# doan2.net
KiCad netlist of a schematic drawn in Altium Designer
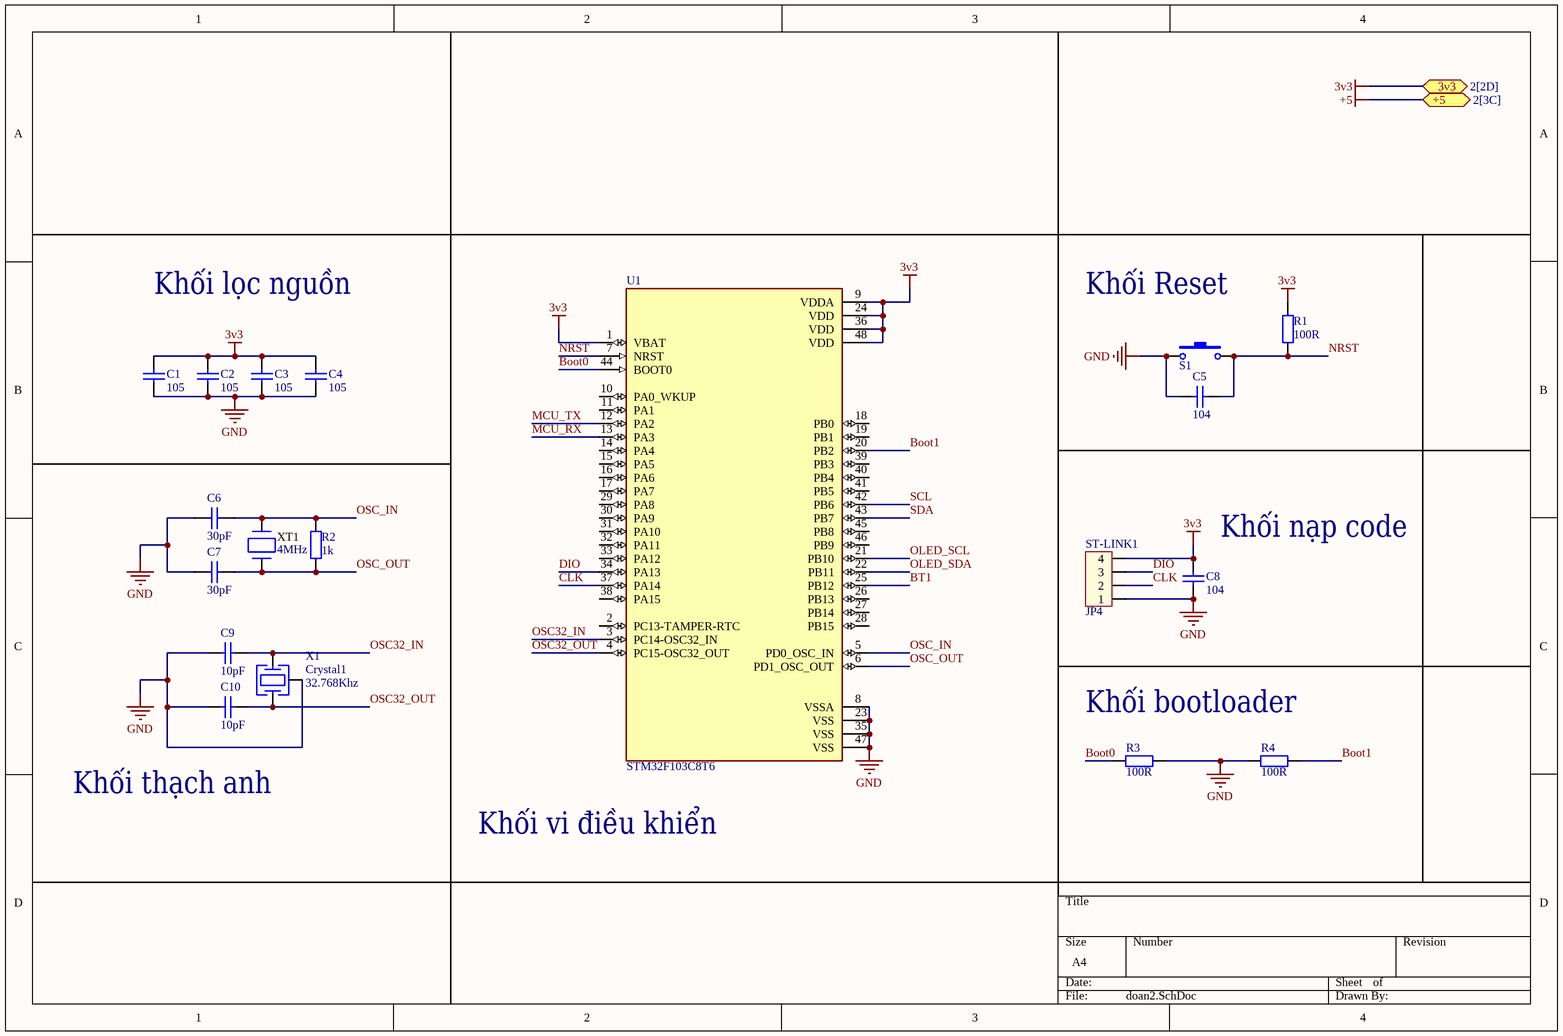
[diagram p0: doan2.SchDoc]

(export (version "E")
  (design (tool "Eeschema 10.0.6"))
  (components
    (comp (ref "C1")
      (value "105")
      (footprint "C-NP-0805")
      (description "Non-polarized Capacitor")
      (fields (field (name "Comment") "Cap Non-pol") (field (name "PUBLISHER") "Altium Limited"))
      (libsource (lib "Kiet") (part "Cap Non-pol"))
    )
    (comp (ref "C2")
      (value "105")
      (footprint "C-NP-0805")
      (description "Non-polarized Capacitor")
      (fields (field (name "Comment") "Cap Non-pol") (field (name "PUBLISHER") "Altium Limited"))
      (libsource (lib "Kiet") (part "Cap Non-pol"))
    )
    (comp (ref "C3")
      (value "105")
      (footprint "C-NP-0805")
      (description "Non-polarized Capacitor")
      (fields (field (name "Comment") "Cap Non-pol") (field (name "PUBLISHER") "Altium Limited"))
      (libsource (lib "Kiet") (part "Cap Non-pol"))
    )
    (comp (ref "C4")
      (value "105")
      (footprint "C-NP-0805")
      (description "Non-polarized Capacitor")
      (fields (field (name "Comment") "Cap Non-pol") (field (name "PUBLISHER") "Altium Limited"))
      (libsource (lib "Kiet") (part "Cap Non-pol"))
    )
    (comp (ref "C5")
      (value "104")
      (footprint "C-NP-0805")
      (description "Non-polarized Capacitor")
      (fields (field (name "Comment") "Cap Non-pol") (field (name "PUBLISHER") "Altium Limited"))
      (libsource (lib "Kiet") (part "Cap Non-pol"))
    )
    (comp (ref "C6")
      (value "30pF")
      (footprint "C-NP-0805")
      (description "Non-polarized Capacitor")
      (fields (field (name "Comment") "Cap Non-pol") (field (name "PUBLISHER") "Altium Limited"))
      (libsource (lib "Kiet") (part "Cap Non-pol"))
    )
    (comp (ref "C7")
      (value "30pF")
      (footprint "C-NP-0805")
      (description "Non-polarized Capacitor")
      (fields (field (name "Comment") "Cap Non-pol") (field (name "PUBLISHER") "Altium Limited"))
      (libsource (lib "Kiet") (part "Cap Non-pol"))
    )
    (comp (ref "C8")
      (value "104")
      (footprint "C-NP-0805")
      (description "Non-polarized Capacitor")
      (fields (field (name "Comment") "Cap Non-pol") (field (name "PUBLISHER") "Altium Limited"))
      (libsource (lib "Kiet") (part "Cap Non-pol"))
    )
    (comp (ref "C9")
      (value "10pF")
      (footprint "C-NP-0805")
      (description "Non-polarized Capacitor")
      (fields (field (name "Comment") "Cap Non-pol") (field (name "PUBLISHER") "Altium Limited"))
      (libsource (lib "Kiet") (part "Cap Non-pol"))
    )
    (comp (ref "C10")
      (value "10pF")
      (footprint "C-NP-0805")
      (description "Non-polarized Capacitor")
      (fields (field (name "Comment") "Cap Non-pol") (field (name "PUBLISHER") "Altium Limited"))
      (libsource (lib "Kiet") (part "Cap Non-pol"))
    )
    (comp (ref "R1")
      (value "100R")
      (footprint "DIEN TRO 0805")
      (description "RES_0805")
      (fields (field (name "Comment") "RES_SMD_0805") (field (name "PUBLISHER") "Altium Limited"))
      (libsource (lib "Kiet") (part "RES_SMD_0805"))
    )
    (comp (ref "R2")
      (value "1k")
      (footprint "DIEN TRO 0805")
      (description "RES_0805")
      (fields (field (name "Comment") "RES_SMD_0805") (field (name "PUBLISHER") "Altium Limited"))
      (libsource (lib "Kiet") (part "RES_SMD_0805"))
    )
    (comp (ref "R3")
      (value "100R")
      (footprint "DIEN TRO 0805")
      (description "RES_0805")
      (fields (field (name "Comment") "RES_SMD_0805") (field (name "PUBLISHER") "Altium Limited"))
      (libsource (lib "") (part "RES_SMD_0805_1"))
    )
    (comp (ref "R4")
      (value "100R")
      (footprint "DIEN TRO 0805")
      (description "RES_0805")
      (fields (field (name "Comment") "RES_SMD_0805") (field (name "PUBLISHER") "Altium Limited"))
      (libsource (lib "") (part "RES_SMD_0805_1"))
    )
    (comp (ref "S1")
      (value "SW-SMD")
      (footprint "SW-SMD")
      (description "Switch")
      (fields (field (name "PUBLISHER") "Altium Limited"))
      (libsource (lib "Kiet") (part "SW-SMD"))
    )
    (comp (ref "ST-LINK1")
      (value "JP4")
      (footprint "CON4")
      (description "Connector 4")
      (libsource (lib "Kiet") (part "Con4"))
    )
    (comp (ref "U1")
      (value "STM32F103C8T6")
      (footprint "QFP50P900X900X160-48N")
      (description "ARM® Cortex®-M3 STM32F1 Microcontroller IC 32-Bit 72MHz 64KB (64K x 8) FLASH 48-LQFP (7x7)")
      (fields (field (name "MF") "STMicroelectronics"))
      (libsource (lib "STM32F103C8T6") (part "STM32F103C8T6"))
    )
    (comp (ref "X1")
      (value "Crystal1")
      (footprint "Crystal cylinder")
      (description "Tuning Forl Crystal Units (SMD-Cylinder Type)")
      (fields (field (name "ALTIUM_VALUE") "32.768Khz") (field (name "PUBLISHER") "Hoang Nguyen"))
      (libsource (lib "Kiet") (part "Crystal1"))
    )
    (comp (ref "XT1")
      (value "4MHz")
      (footprint "Crystal.HC49/USxx")
      (description "Quarz Crystal")
      (fields (field (name "Comment") "Crystal2") (field (name "PUBLISHER") "Hoang Nguyen"))
      (libsource (lib "Kiet") (part "Crystal2"))
    )
  )
  (nets
    (net (code "2") (name "/BT1") (class "Default")
      (node (ref "U1") (pin "25") (pinfunction "PB12_25") (pintype "bidirectional"))
    )
    (net (code "3") (name "/Boot0") (class "Default")
      (node (ref "R3") (pin "1") (pinfunction "1_1") (pintype "passive"))
      (node (ref "U1") (pin "44") (pinfunction "BOOT0_44") (pintype "input"))
    )
    (net (code "4") (name "/Boot1") (class "Default")
      (node (ref "R4") (pin "2") (pinfunction "2_2") (pintype "passive"))
      (node (ref "U1") (pin "20") (pinfunction "PB2_20") (pintype "bidirectional"))
    )
    (net (code "5") (name "/CLK") (class "Default")
      (node (ref "ST-LINK1") (pin "2") (pinfunction "2_2") (pintype "passive"))
      (node (ref "U1") (pin "37") (pinfunction "PA14_37") (pintype "bidirectional"))
    )
    (net (code "6") (name "/DIO") (class "Default")
      (node (ref "ST-LINK1") (pin "3") (pinfunction "3_3") (pintype "passive"))
      (node (ref "U1") (pin "34") (pinfunction "PA13_34") (pintype "bidirectional"))
    )
    (net (code "7") (name "/MCU_RX") (class "Default")
      (node (ref "U1") (pin "13") (pinfunction "PA3_13") (pintype "bidirectional"))
    )
    (net (code "8") (name "/MCU_TX") (class "Default")
      (node (ref "U1") (pin "12") (pinfunction "PA2_12") (pintype "bidirectional"))
    )
    (net (code "9") (name "/NRST") (class "Default")
      (node (ref "C5") (pin "1") (pinfunction "1_1") (pintype "passive"))
      (node (ref "R1") (pin "1") (pinfunction "1_1") (pintype "passive"))
      (node (ref "S1") (pin "2") (pinfunction "2_2") (pintype "passive"))
      (node (ref "U1") (pin "7") (pinfunction "NRST_7") (pintype "input"))
    )
    (net (code "10") (name "/OLED_SCL") (class "Default")
      (node (ref "U1") (pin "21") (pinfunction "PB10_21") (pintype "bidirectional"))
    )
    (net (code "11") (name "/OLED_SDA") (class "Default")
      (node (ref "U1") (pin "22") (pinfunction "PB11_22") (pintype "bidirectional"))
    )
    (net (code "12") (name "/OSC32_IN") (class "Default")
      (node (ref "C9") (pin "1") (pinfunction "1_1") (pintype "passive"))
      (node (ref "U1") (pin "3") (pinfunction "PC14-OSC32_IN_3") (pintype "bidirectional"))
      (node (ref "X1") (pin "2") (pintype "passive"))
    )
    (net (code "13") (name "/OSC32_OUT") (class "Default")
      (node (ref "C10") (pin "1") (pinfunction "1_1") (pintype "passive"))
      (node (ref "U1") (pin "4") (pinfunction "PC15-OSC32_OUT_4") (pintype "bidirectional"))
      (node (ref "X1") (pin "1") (pintype "passive"))
    )
    (net (code "14") (name "/OSC_IN") (class "Default")
      (node (ref "C6") (pin "1") (pinfunction "1_1") (pintype "passive"))
      (node (ref "R2") (pin "2") (pinfunction "2_2") (pintype "passive"))
      (node (ref "U1") (pin "5") (pinfunction "PD0_OSC_IN_5") (pintype "bidirectional"))
      (node (ref "XT1") (pin "2") (pinfunction "2_2") (pintype "passive"))
    )
    (net (code "15") (name "/OSC_OUT") (class "Default")
      (node (ref "C7") (pin "1") (pinfunction "1_1") (pintype "passive"))
      (node (ref "R2") (pin "1") (pinfunction "1_1") (pintype "passive"))
      (node (ref "U1") (pin "6") (pinfunction "PD1_OSC_OUT_6") (pintype "bidirectional"))
      (node (ref "XT1") (pin "1") (pinfunction "1_1") (pintype "passive"))
    )
    (net (code "16") (name "/SCL") (class "Default")
      (node (ref "U1") (pin "42") (pinfunction "PB6_42") (pintype "bidirectional"))
    )
    (net (code "17") (name "/SDA") (class "Default")
      (node (ref "U1") (pin "43") (pinfunction "PB7_43") (pintype "bidirectional"))
    )
    (net (code "18") (name "3v3") (class "Default")
      (node (ref "C1") (pin "2") (pinfunction "2_2") (pintype "passive"))
      (node (ref "C2") (pin "2") (pinfunction "2_2") (pintype "passive"))
      (node (ref "C3") (pin "2") (pinfunction "2_2") (pintype "passive"))
      (node (ref "C4") (pin "2") (pinfunction "2_2") (pintype "passive"))
      (node (ref "C8") (pin "1") (pinfunction "1_1") (pintype "passive"))
      (node (ref "R1") (pin "2") (pinfunction "2_2") (pintype "passive"))
      (node (ref "ST-LINK1") (pin "4") (pinfunction "4_4") (pintype "passive"))
      (node (ref "U1") (pin "1") (pinfunction "VBAT_1") (pintype "bidirectional"))
      (node (ref "U1") (pin "24") (pinfunction "VDD_24") (pintype "power_in"))
      (node (ref "U1") (pin "36") (pinfunction "VDD_36") (pintype "power_in"))
      (node (ref "U1") (pin "48") (pinfunction "VDD_48") (pintype "power_in"))
      (node (ref "U1") (pin "9") (pinfunction "VDDA_9") (pintype "power_in"))
    )
    (net (code "19") (name "GND") (class "Default")
      (node (ref "C1") (pin "1") (pinfunction "1_1") (pintype "passive"))
      (node (ref "C10") (pin "2") (pinfunction "2_2") (pintype "passive"))
      (node (ref "C2") (pin "1") (pinfunction "1_1") (pintype "passive"))
      (node (ref "C3") (pin "1") (pinfunction "1_1") (pintype "passive"))
      (node (ref "C4") (pin "1") (pinfunction "1_1") (pintype "passive"))
      (node (ref "C5") (pin "2") (pinfunction "2_2") (pintype "passive"))
      (node (ref "C6") (pin "2") (pinfunction "2_2") (pintype "passive"))
      (node (ref "C7") (pin "2") (pinfunction "2_2") (pintype "passive"))
      (node (ref "C8") (pin "2") (pinfunction "2_2") (pintype "passive"))
      (node (ref "C9") (pin "2") (pinfunction "2_2") (pintype "passive"))
      (node (ref "R3") (pin "2") (pinfunction "2_2") (pintype "passive"))
      (node (ref "R4") (pin "1") (pinfunction "1_1") (pintype "passive"))
      (node (ref "S1") (pin "1") (pinfunction "1_1") (pintype "passive"))
      (node (ref "ST-LINK1") (pin "1") (pinfunction "1_1") (pintype "passive"))
      (node (ref "U1") (pin "23") (pinfunction "VSS_23") (pintype "power_in"))
      (node (ref "U1") (pin "35") (pinfunction "VSS_35") (pintype "power_in"))
      (node (ref "U1") (pin "47") (pinfunction "VSS_47") (pintype "power_in"))
      (node (ref "U1") (pin "8") (pinfunction "VSSA_8") (pintype "power_in"))
      (node (ref "X1") (pin "3") (pinfunction "GND_3") (pintype "passive"))
    )
    (net (code "20") (name "unconnected-(U1-PA0_WKUP-Pad10)") (class "Default")
      (node (ref "U1") (pin "10") (pinfunction "PA0_WKUP_10") (pintype "bidirectional"))
    )
    (net (code "21") (name "unconnected-(U1-PA1-Pad11)") (class "Default")
      (node (ref "U1") (pin "11") (pinfunction "PA1_11") (pintype "bidirectional"))
    )
    (net (code "22") (name "unconnected-(U1-PA4-Pad14)") (class "Default")
      (node (ref "U1") (pin "14") (pinfunction "PA4_14") (pintype "bidirectional"))
    )
    (net (code "23") (name "unconnected-(U1-PA5-Pad15)") (class "Default")
      (node (ref "U1") (pin "15") (pinfunction "PA5_15") (pintype "bidirectional"))
    )
    (net (code "24") (name "unconnected-(U1-PA6-Pad16)") (class "Default")
      (node (ref "U1") (pin "16") (pinfunction "PA6_16") (pintype "bidirectional"))
    )
    (net (code "25") (name "unconnected-(U1-PA7-Pad17)") (class "Default")
      (node (ref "U1") (pin "17") (pinfunction "PA7_17") (pintype "bidirectional"))
    )
    (net (code "26") (name "unconnected-(U1-PA8-Pad29)") (class "Default")
      (node (ref "U1") (pin "29") (pinfunction "PA8_29") (pintype "bidirectional"))
    )
    (net (code "27") (name "unconnected-(U1-PA9-Pad30)") (class "Default")
      (node (ref "U1") (pin "30") (pinfunction "PA9_30") (pintype "bidirectional"))
    )
    (net (code "28") (name "unconnected-(U1-PA10-Pad31)") (class "Default")
      (node (ref "U1") (pin "31") (pinfunction "PA10_31") (pintype "bidirectional"))
    )
    (net (code "29") (name "unconnected-(U1-PA11-Pad32)") (class "Default")
      (node (ref "U1") (pin "32") (pinfunction "PA11_32") (pintype "bidirectional"))
    )
    (net (code "30") (name "unconnected-(U1-PA12-Pad33)") (class "Default")
      (node (ref "U1") (pin "33") (pinfunction "PA12_33") (pintype "bidirectional"))
    )
    (net (code "31") (name "unconnected-(U1-PA15-Pad38)") (class "Default")
      (node (ref "U1") (pin "38") (pinfunction "PA15_38") (pintype "bidirectional"))
    )
    (net (code "32") (name "unconnected-(U1-PB0-Pad18)") (class "Default")
      (node (ref "U1") (pin "18") (pinfunction "PB0_18") (pintype "bidirectional"))
    )
    (net (code "33") (name "unconnected-(U1-PB1-Pad19)") (class "Default")
      (node (ref "U1") (pin "19") (pinfunction "PB1_19") (pintype "bidirectional"))
    )
    (net (code "34") (name "unconnected-(U1-PB3-Pad39)") (class "Default")
      (node (ref "U1") (pin "39") (pinfunction "PB3_39") (pintype "bidirectional"))
    )
    (net (code "35") (name "unconnected-(U1-PB4-Pad40)") (class "Default")
      (node (ref "U1") (pin "40") (pinfunction "PB4_40") (pintype "bidirectional"))
    )
    (net (code "36") (name "unconnected-(U1-PB5-Pad41)") (class "Default")
      (node (ref "U1") (pin "41") (pinfunction "PB5_41") (pintype "bidirectional"))
    )
    (net (code "37") (name "unconnected-(U1-PB8-Pad45)") (class "Default")
      (node (ref "U1") (pin "45") (pinfunction "PB8_45") (pintype "bidirectional"))
    )
    (net (code "38") (name "unconnected-(U1-PB9-Pad46)") (class "Default")
      (node (ref "U1") (pin "46") (pinfunction "PB9_46") (pintype "bidirectional"))
    )
    (net (code "39") (name "unconnected-(U1-PB13-Pad26)") (class "Default")
      (node (ref "U1") (pin "26") (pinfunction "PB13_26") (pintype "bidirectional"))
    )
    (net (code "40") (name "unconnected-(U1-PB14-Pad27)") (class "Default")
      (node (ref "U1") (pin "27") (pinfunction "PB14_27") (pintype "bidirectional"))
    )
    (net (code "41") (name "unconnected-(U1-PB15-Pad28)") (class "Default")
      (node (ref "U1") (pin "28") (pinfunction "PB15_28") (pintype "bidirectional"))
    )
    (net (code "42") (name "unconnected-(U1-PC13-TAMPER-RTC-Pad2)") (class "Default")
      (node (ref "U1") (pin "2") (pinfunction "PC13-TAMPER-RTC_2") (pintype "bidirectional"))
    )
  )
)
